# 4069-Twin-T-Drums.net
KiCad netlist of a schematic drawn in EAGLE
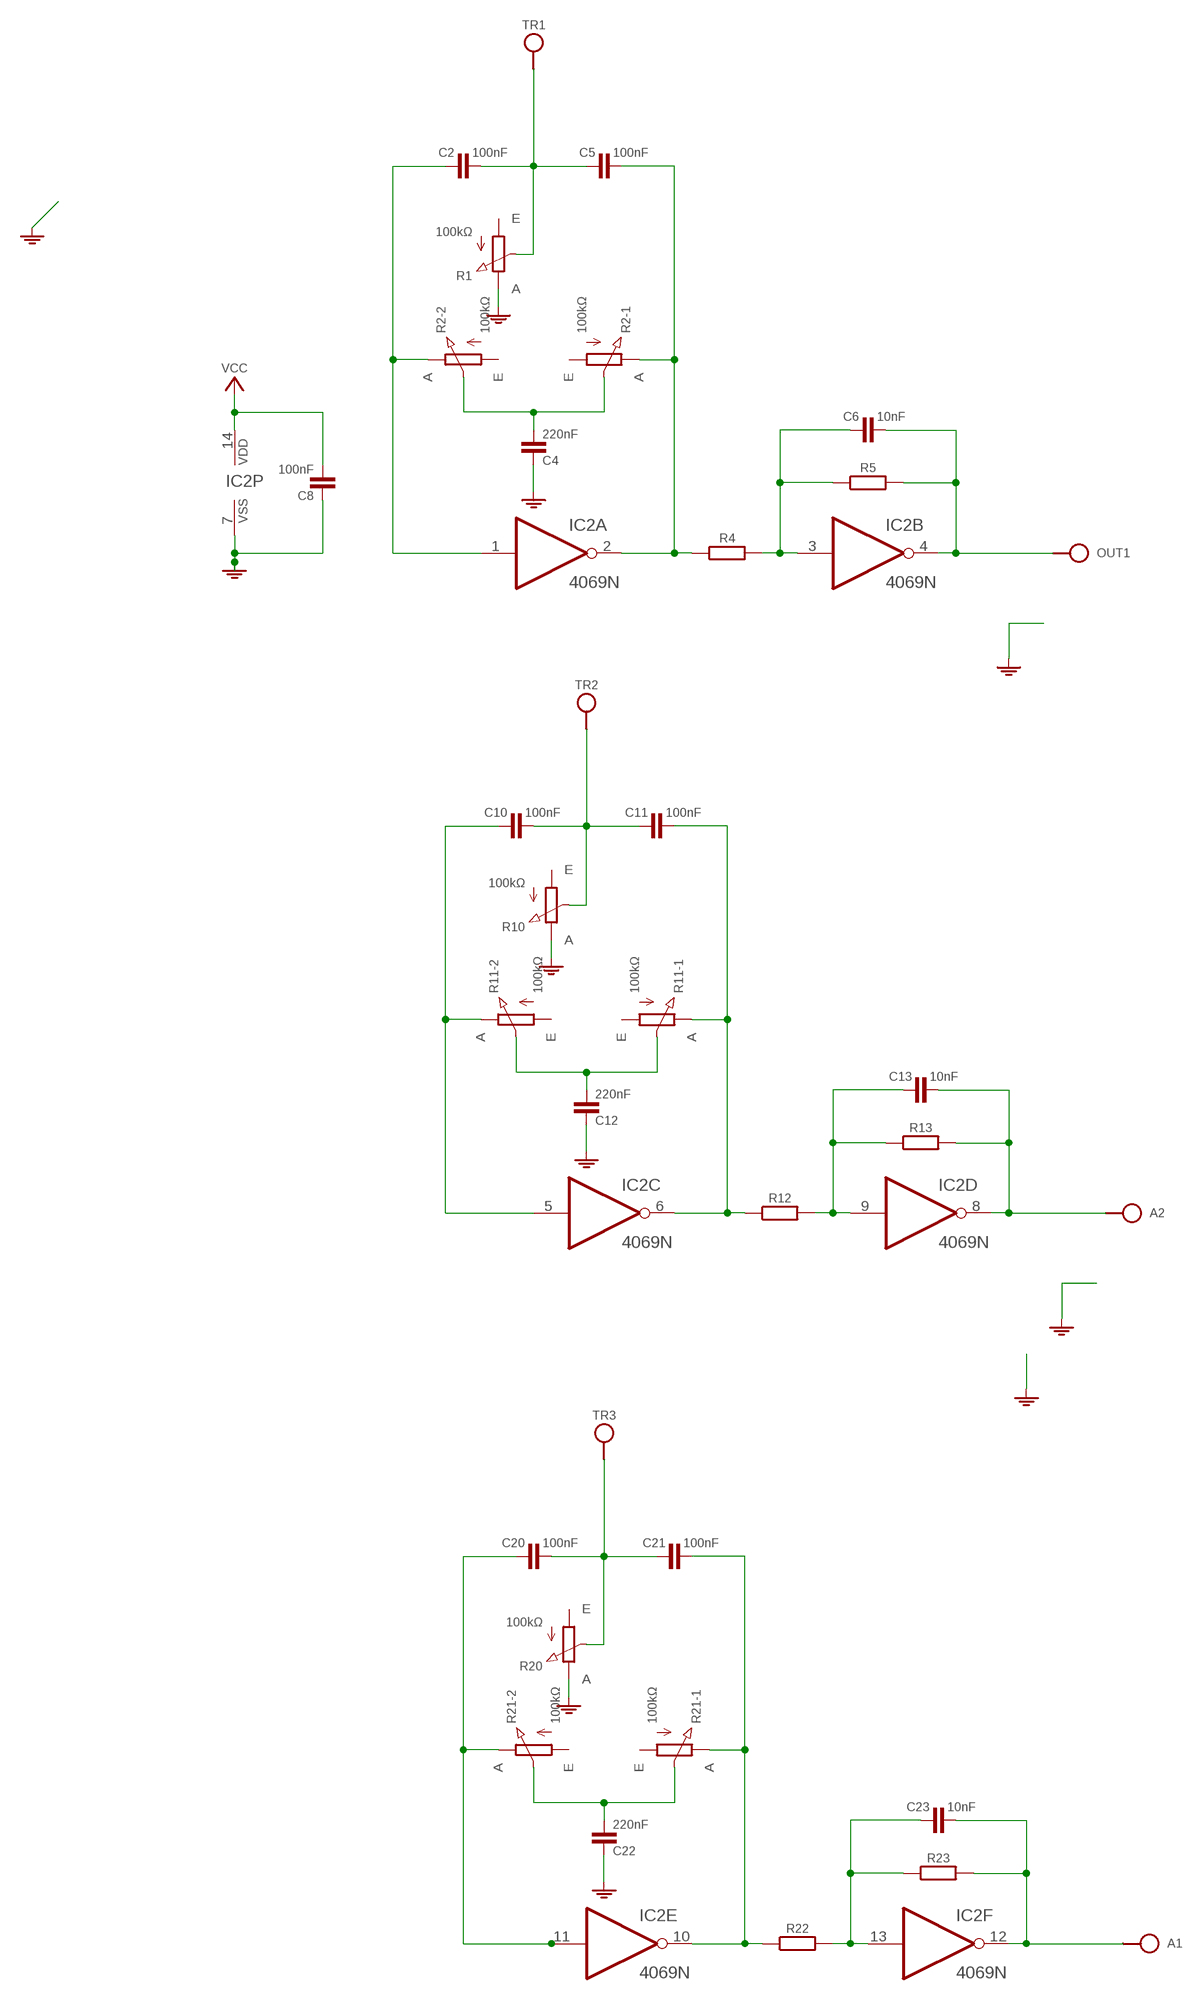
[diagram p0: schematic, sheet 1]

(export (version "E")
  (design (tool "Eeschema 10.0.6"))
  (components
    (comp (ref "A1")
      (value "HPORT")
      (footprint "eagle-import:SPAD")
      (libsource (lib "eagle-import") (part "HPORT"))
    )
    (comp (ref "A2")
      (value "HPORT")
      (footprint "eagle-import:SPAD")
      (libsource (lib "eagle-import") (part "HPORT"))
    )
    (comp (ref "C2")
      (value "100nF")
      (footprint "eagle-import:C050-020X044")
      (libsource (lib "eagle-import") (part "C-H050-020X044"))
    )
    (comp (ref "C4")
      (value "220nF")
      (footprint "eagle-import:C050-020X044_V")
      (libsource (lib "eagle-import") (part "C050-020X044/V"))
    )
    (comp (ref "C5")
      (value "100nF")
      (footprint "eagle-import:C050-020X044")
      (libsource (lib "eagle-import") (part "C-H050-020X044"))
    )
    (comp (ref "C6")
      (value "10nF")
      (footprint "eagle-import:C025-015X024")
      (libsource (lib "eagle-import") (part "C-H025-015X024"))
    )
    (comp (ref "C8")
      (value "100nF")
      (footprint "eagle-import:C050-020X044_V")
      (libsource (lib "eagle-import") (part "C050-020X044/V"))
    )
    (comp (ref "C10")
      (value "100nF")
      (footprint "eagle-import:C050-020X044")
      (libsource (lib "eagle-import") (part "C-H050-020X044"))
    )
    (comp (ref "C11")
      (value "100nF")
      (footprint "eagle-import:C050-020X044")
      (libsource (lib "eagle-import") (part "C-H050-020X044"))
    )
    (comp (ref "C12")
      (value "220nF")
      (footprint "eagle-import:C050-020X044_V")
      (libsource (lib "eagle-import") (part "C050-020X044/V"))
    )
    (comp (ref "C13")
      (value "10nF")
      (footprint "eagle-import:C025-015X024")
      (libsource (lib "eagle-import") (part "C-H025-015X024"))
    )
    (comp (ref "C20")
      (value "100nF")
      (footprint "eagle-import:C050-020X044")
      (libsource (lib "eagle-import") (part "C-H050-020X044"))
    )
    (comp (ref "C21")
      (value "100nF")
      (footprint "eagle-import:C050-020X044")
      (libsource (lib "eagle-import") (part "C-H050-020X044"))
    )
    (comp (ref "C22")
      (value "220nF")
      (footprint "eagle-import:C050-020X044_V")
      (libsource (lib "eagle-import") (part "C050-020X044/V"))
    )
    (comp (ref "C23")
      (value "10nF")
      (footprint "eagle-import:C025-015X024")
      (libsource (lib "eagle-import") (part "C-H025-015X024"))
    )
    (comp (ref "IC2")
      (value "4069N")
      (footprint "eagle-import:DIL14")
      (libsource (lib "eagle-import") (part "4069N"))
    )
    (comp (ref "OUT1")
      (value "HPORT")
      (footprint "eagle-import:SPAD")
      (libsource (lib "eagle-import") (part "HPORT"))
    )
    (comp (ref "R1")
      (value "100kΩ")
      (footprint "eagle-import:POT")
      (libsource (lib "eagle-import") (part "POT"))
    )
    (comp (ref "R2")
      (value "100kΩ")
      (footprint "eagle-import:POT-STEREO-2X3")
      (libsource (lib "eagle-import") (part "POT-STEREO"))
    )
    (comp (ref "R4")
      (value "R-H0202/2V")
      (footprint "eagle-import:0202_2V")
      (libsource (lib "eagle-import") (part "R-H0202/2V"))
    )
    (comp (ref "R5")
      (value "R-H0202/2V")
      (footprint "eagle-import:0202_2V")
      (libsource (lib "eagle-import") (part "R-H0202/2V"))
    )
    (comp (ref "R10")
      (value "100kΩ")
      (footprint "eagle-import:POT")
      (libsource (lib "eagle-import") (part "POT"))
    )
    (comp (ref "R11")
      (value "100kΩ")
      (footprint "eagle-import:POT-STEREO-2X3")
      (libsource (lib "eagle-import") (part "POT-STEREO"))
    )
    (comp (ref "R12")
      (value "R-H0202/2")
      (footprint "eagle-import:0202_2")
      (libsource (lib "eagle-import") (part "R-H0202/2"))
    )
    (comp (ref "R13")
      (value "R-H0202/2V")
      (footprint "eagle-import:0202_2V")
      (libsource (lib "eagle-import") (part "R-H0202/2V"))
    )
    (comp (ref "R20")
      (value "100kΩ")
      (footprint "eagle-import:POT")
      (libsource (lib "eagle-import") (part "POT"))
    )
    (comp (ref "R21")
      (value "100kΩ")
      (footprint "eagle-import:POT-STEREO-2X3")
      (libsource (lib "eagle-import") (part "POT-STEREO"))
    )
    (comp (ref "R22")
      (value "R-H0202/2V")
      (footprint "eagle-import:0202_2V")
      (libsource (lib "eagle-import") (part "R-H0202/2V"))
    )
    (comp (ref "R23")
      (value "R-H0202/2V")
      (footprint "eagle-import:0202_2V")
      (libsource (lib "eagle-import") (part "R-H0202/2V"))
    )
    (comp (ref "S12")
      (value "VCC_GNDPWR-L")
      (footprint "eagle-import:PWR-L")
      (libsource (lib "eagle-import") (part "VCC_GNDPWR-L"))
    )
    (comp (ref "TR1")
      (value "VPORT")
      (footprint "eagle-import:SPAD")
      (libsource (lib "eagle-import") (part "VPORT"))
    )
    (comp (ref "TR2")
      (value "VPORT")
      (footprint "eagle-import:SPAD")
      (libsource (lib "eagle-import") (part "VPORT"))
    )
    (comp (ref "TR3")
      (value "VPORT")
      (footprint "eagle-import:SPAD")
      (libsource (lib "eagle-import") (part "VPORT"))
    )
  )
  (nets
    (net (code "1") (name "GND") (class "Default")
      (node (ref "C12") (pin "1") (pinfunction "1_1") (pintype "passive"))
      (node (ref "C22") (pin "1") (pinfunction "1_1") (pintype "passive"))
      (node (ref "C4") (pin "1") (pinfunction "1_1") (pintype "passive"))
      (node (ref "C8") (pin "1") (pinfunction "1_1") (pintype "passive"))
      (node (ref "IC2") (pin "7") (pinfunction "VSS_7") (pintype "power_in"))
      (node (ref "R1") (pin "E") (pinfunction "E_E") (pintype "passive"))
      (node (ref "R10") (pin "E") (pinfunction "E_E") (pintype "passive"))
      (node (ref "R20") (pin "E") (pinfunction "E_E") (pintype "passive"))
      (node (ref "S12") (pin "1") (pinfunction "GND_1") (pintype "power_in"))
    )
    (net (code "2") (name "Net-(A1-P$1)") (class "Default")
      (node (ref "A1") (pin "1") (pinfunction "P$1_1") (pintype "passive"))
      (node (ref "C23") (pin "2") (pinfunction "2_2") (pintype "passive"))
      (node (ref "IC2") (pin "12") (pinfunction "O_12") (pintype "output"))
      (node (ref "R23") (pin "2") (pinfunction "2_2") (pintype "passive"))
    )
    (net (code "3") (name "Net-(A2-P$1)") (class "Default")
      (node (ref "A2") (pin "1") (pinfunction "P$1_1") (pintype "passive"))
      (node (ref "C13") (pin "2") (pinfunction "2_2") (pintype "passive"))
      (node (ref "IC2") (pin "8") (pinfunction "O_8") (pintype "output"))
      (node (ref "R13") (pin "2") (pinfunction "2_2") (pintype "passive"))
    )
    (net (code "4") (name "Net-(IC2A-I)") (class "Default")
      (node (ref "C2") (pin "1") (pinfunction "1_1") (pintype "passive"))
      (node (ref "IC2") (pin "1") (pinfunction "I_1") (pintype "input"))
      (node (ref "R2") (pin "2-E") (pinfunction "E_2-E") (pintype "passive"))
    )
    (net (code "5") (name "Net-(IC2A-O)") (class "Default")
      (node (ref "C5") (pin "2") (pinfunction "2_2") (pintype "passive"))
      (node (ref "IC2") (pin "2") (pinfunction "O_2") (pintype "output"))
      (node (ref "R2") (pin "1-E") (pinfunction "E_1-E") (pintype "passive"))
      (node (ref "R4") (pin "1") (pinfunction "1_1") (pintype "passive"))
    )
    (net (code "6") (name "Net-(IC2B-I)") (class "Default")
      (node (ref "C6") (pin "1") (pinfunction "1_1") (pintype "passive"))
      (node (ref "IC2") (pin "3") (pinfunction "I_3") (pintype "input"))
      (node (ref "R4") (pin "2") (pinfunction "2_2") (pintype "passive"))
      (node (ref "R5") (pin "1") (pinfunction "1_1") (pintype "passive"))
    )
    (net (code "7") (name "Net-(IC2B-O)") (class "Default")
      (node (ref "C6") (pin "2") (pinfunction "2_2") (pintype "passive"))
      (node (ref "IC2") (pin "4") (pinfunction "O_4") (pintype "output"))
      (node (ref "OUT1") (pin "1") (pinfunction "P$1_1") (pintype "passive"))
      (node (ref "R5") (pin "2") (pinfunction "2_2") (pintype "passive"))
    )
    (net (code "8") (name "Net-(IC2C-I)") (class "Default")
      (node (ref "C10") (pin "1") (pinfunction "1_1") (pintype "passive"))
      (node (ref "IC2") (pin "5") (pinfunction "I_5") (pintype "input"))
      (node (ref "R11") (pin "2-E") (pinfunction "E_2-E") (pintype "passive"))
    )
    (net (code "9") (name "Net-(IC2C-O)") (class "Default")
      (node (ref "C11") (pin "2") (pinfunction "2_2") (pintype "passive"))
      (node (ref "IC2") (pin "6") (pinfunction "O_6") (pintype "output"))
      (node (ref "R11") (pin "1-E") (pinfunction "E_1-E") (pintype "passive"))
      (node (ref "R12") (pin "1") (pinfunction "1_1") (pintype "passive"))
    )
    (net (code "10") (name "Net-(IC2D-I)") (class "Default")
      (node (ref "C13") (pin "1") (pinfunction "1_1") (pintype "passive"))
      (node (ref "IC2") (pin "9") (pinfunction "I_9") (pintype "input"))
      (node (ref "R12") (pin "2") (pinfunction "2_2") (pintype "passive"))
      (node (ref "R13") (pin "1") (pinfunction "1_1") (pintype "passive"))
    )
    (net (code "11") (name "Net-(IC2E-I)") (class "Default")
      (node (ref "C20") (pin "1") (pinfunction "1_1") (pintype "passive"))
      (node (ref "IC2") (pin "11") (pinfunction "I_11") (pintype "input"))
      (node (ref "R21") (pin "2-E") (pinfunction "E_2-E") (pintype "passive"))
    )
    (net (code "12") (name "Net-(IC2E-O)") (class "Default")
      (node (ref "C21") (pin "2") (pinfunction "2_2") (pintype "passive"))
      (node (ref "IC2") (pin "10") (pinfunction "O_10") (pintype "output"))
      (node (ref "R21") (pin "1-E") (pinfunction "E_1-E") (pintype "passive"))
      (node (ref "R22") (pin "1") (pinfunction "1_1") (pintype "passive"))
    )
    (net (code "13") (name "Net-(IC2F-I)") (class "Default")
      (node (ref "C23") (pin "1") (pinfunction "1_1") (pintype "passive"))
      (node (ref "IC2") (pin "13") (pinfunction "I_13") (pintype "input"))
      (node (ref "R22") (pin "2") (pinfunction "2_2") (pintype "passive"))
      (node (ref "R23") (pin "1") (pinfunction "1_1") (pintype "passive"))
    )
    (net (code "14") (name "Net-(IC2G-VDD)") (class "Default")
      (node (ref "C8") (pin "2") (pinfunction "2_2") (pintype "passive"))
      (node (ref "IC2") (pin "14") (pinfunction "VDD_14") (pintype "power_in"))
      (node (ref "S12") (pin "2") (pinfunction "VCC_2") (pintype "power_in"))
    )
    (net (code "15") (name "Net-(R2A-S)") (class "Default")
      (node (ref "C4") (pin "2") (pinfunction "2_2") (pintype "passive"))
      (node (ref "R2") (pin "1-S") (pinfunction "S_1-S") (pintype "passive"))
      (node (ref "R2") (pin "2-S") (pinfunction "S_2-S") (pintype "passive"))
    )
    (net (code "16") (name "Net-(R11A-S)") (class "Default")
      (node (ref "C12") (pin "2") (pinfunction "2_2") (pintype "passive"))
      (node (ref "R11") (pin "1-S") (pinfunction "S_1-S") (pintype "passive"))
      (node (ref "R11") (pin "2-S") (pinfunction "S_2-S") (pintype "passive"))
    )
    (net (code "17") (name "Net-(R21A-S)") (class "Default")
      (node (ref "C22") (pin "2") (pinfunction "2_2") (pintype "passive"))
      (node (ref "R21") (pin "1-S") (pinfunction "S_1-S") (pintype "passive"))
      (node (ref "R21") (pin "2-S") (pinfunction "S_2-S") (pintype "passive"))
    )
    (net (code "18") (name "Net-(TR1-P$1)") (class "Default")
      (node (ref "C2") (pin "2") (pinfunction "2_2") (pintype "passive"))
      (node (ref "C5") (pin "1") (pinfunction "1_1") (pintype "passive"))
      (node (ref "R1") (pin "S") (pinfunction "S_S") (pintype "passive"))
      (node (ref "TR1") (pin "1") (pinfunction "P$1_1") (pintype "passive"))
    )
    (net (code "19") (name "Net-(TR2-P$1)") (class "Default")
      (node (ref "C10") (pin "2") (pinfunction "2_2") (pintype "passive"))
      (node (ref "C11") (pin "1") (pinfunction "1_1") (pintype "passive"))
      (node (ref "R10") (pin "S") (pinfunction "S_S") (pintype "passive"))
      (node (ref "TR2") (pin "1") (pinfunction "P$1_1") (pintype "passive"))
    )
    (net (code "20") (name "Net-(TR3-P$1)") (class "Default")
      (node (ref "C20") (pin "2") (pinfunction "2_2") (pintype "passive"))
      (node (ref "C21") (pin "1") (pinfunction "1_1") (pintype "passive"))
      (node (ref "R20") (pin "S") (pinfunction "S_S") (pintype "passive"))
      (node (ref "TR3") (pin "1") (pinfunction "P$1_1") (pintype "passive"))
    )
    (net (code "21") (name "unconnected-(R1-PadA)") (class "Default")
      (node (ref "R1") (pin "A") (pinfunction "A_A") (pintype "passive"))
    )
    (net (code "22") (name "unconnected-(R2A-A-Pad1-A)") (class "Default")
      (node (ref "R2") (pin "1-A") (pinfunction "A_1-A") (pintype "passive"))
    )
    (net (code "23") (name "unconnected-(R2B-A-Pad2-A)") (class "Default")
      (node (ref "R2") (pin "2-A") (pinfunction "A_2-A") (pintype "passive"))
    )
    (net (code "24") (name "unconnected-(R10-PadA)") (class "Default")
      (node (ref "R10") (pin "A") (pinfunction "A_A") (pintype "passive"))
    )
    (net (code "25") (name "unconnected-(R11A-A-Pad1-A)") (class "Default")
      (node (ref "R11") (pin "1-A") (pinfunction "A_1-A") (pintype "passive"))
    )
    (net (code "26") (name "unconnected-(R11B-A-Pad2-A)") (class "Default")
      (node (ref "R11") (pin "2-A") (pinfunction "A_2-A") (pintype "passive"))
    )
    (net (code "27") (name "unconnected-(R20-PadA)") (class "Default")
      (node (ref "R20") (pin "A") (pinfunction "A_A") (pintype "passive"))
    )
    (net (code "28") (name "unconnected-(R21A-A-Pad1-A)") (class "Default")
      (node (ref "R21") (pin "1-A") (pinfunction "A_1-A") (pintype "passive"))
    )
    (net (code "29") (name "unconnected-(R21B-A-Pad2-A)") (class "Default")
      (node (ref "R21") (pin "2-A") (pinfunction "A_2-A") (pintype "passive"))
    )
  )
)
